# CANOPi_Baseboard_LTE.net
KiCad netlist of a schematic drawn in Altium Designer
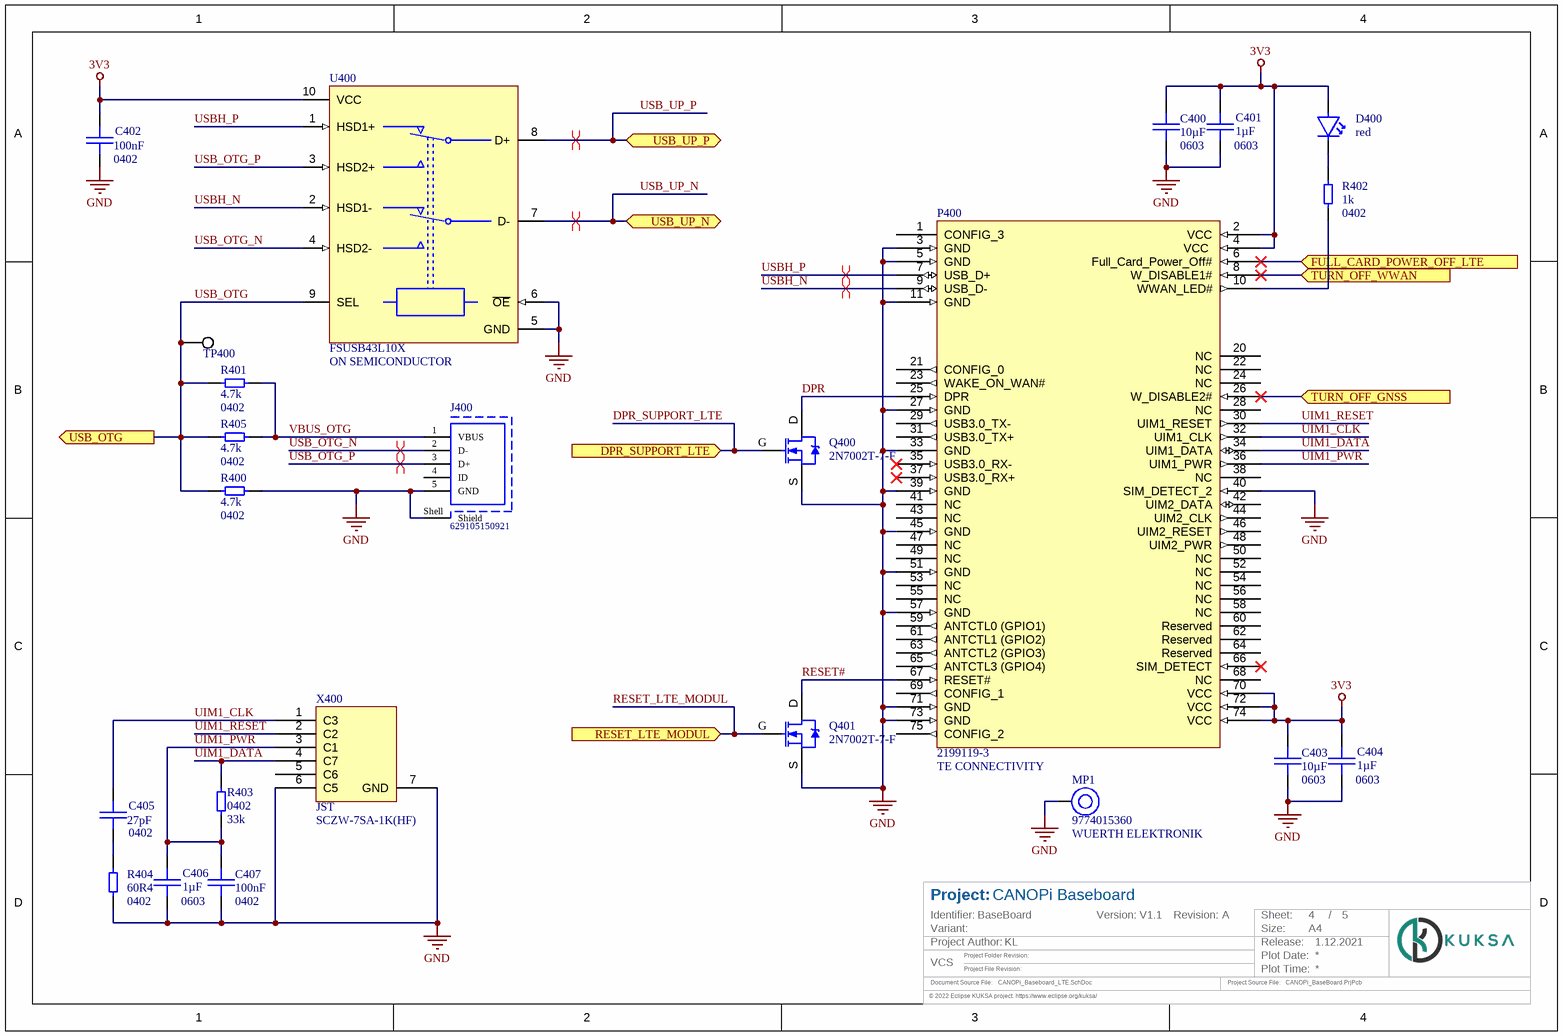
[diagram p0: CANOPi_Baseboard_LTE.SchDoc]

(export (version "E")
  (design (tool "Eeschema 10.0.6"))
  (components
    (comp (ref "C400")
      (value "CAP 0603 10µF -20% +20% 6.3V X5R")
      (footprint "CAP 0603 [1608 Metric] X080 N")
      (description "SMT 10µF ±20% 6,3 V Keramikkondensatoren X5R")
      (fields
        (field (name "MANUFACTURER PART NUMBER") "GRM188R60J106ME84")
        (field (name "CAPACITANCE") "10µF")
        (field (name "MANUFACTURER") "MURATA")
        (field (name "CASE") "0603")
      )
      (libsource (lib "ShareLib") (part "Capacitor non-polarized - Standard Schematic"))
    )
    (comp (ref "C401")
      (value "CAP 0603 1u -10% +10% 10V X7R")
      (footprint "CAP 0603 [1608 Metric] X080 N")
      (description "SMD/SMT 0603 10V -10% +10% X7R - Multilayer Ceramic Capacitors MLCC")
      (fields
        (field (name "CAPACITANCE") "1µF")
        (field (name "MANUFACTURER PART NUMBER") "GRM188R71A105KA61#")
        (field (name "MANUFACTURER") "MURATA")
        (field (name "CASE") "0603")
      )
      (libsource (lib "ShareLib") (part "Capacitor non-polarized - Standard Schematic"))
    )
    (comp (ref "C402")
      (value "CAP 0402 100n -10% +10% 6.3V X7R")
      (footprint "CAP 0402 [1005 Metric] X050 N")
      (description "SMD/SMT 0402 6.3V -10% +10% X7R - Multilayer Ceramic Capacitors MLCC")
      (fields
        (field (name "MANUFACTURER") "MURATA")
        (field (name "CAPACITANCE") "100nF")
        (field (name "MANUFACTURER PART NUMBER") "GRM155R70J104KA01#")
        (field (name "CASE") "0402")
      )
      (libsource (lib "ShareLib") (part "Capacitor non-polarized - Standard Schematic"))
    )
    (comp (ref "C403")
      (value "CAP 0603 10µF -20% +20% 6.3V X5R")
      (footprint "CAP 0603 [1608 Metric] X080 N")
      (description "SMT 10µF ±20% 6,3 V Keramikkondensatoren X5R")
      (fields
        (field (name "MANUFACTURER PART NUMBER") "GRM188R60J106ME84")
        (field (name "CAPACITANCE") "10µF")
        (field (name "MANUFACTURER") "MURATA")
        (field (name "CASE") "0603")
      )
      (libsource (lib "ShareLib") (part "Capacitor non-polarized - Standard Schematic"))
    )
    (comp (ref "C404")
      (value "CAP 0603 1u -10% +10% 10V X7R")
      (footprint "CAP 0603 [1608 Metric] X080 N")
      (description "SMD/SMT 0603 10V -10% +10% X7R - Multilayer Ceramic Capacitors MLCC")
      (fields
        (field (name "CAPACITANCE") "1µF")
        (field (name "MANUFACTURER PART NUMBER") "GRM188R71A105KA61#")
        (field (name "MANUFACTURER") "MURATA")
        (field (name "CASE") "0603")
      )
      (libsource (lib "ShareLib") (part "Capacitor non-polarized - Standard Schematic"))
    )
    (comp (ref "C405")
      (value "CAP 0402 27p -2% +2% 25V C0G")
      (footprint "CAP 0402 [1005 Metric] X050 N")
      (description "SMD/SMT 0402 25V -2% +2% C0G - Multilayer Ceramic Capacitors MLCC")
      (fields
        (field (name "MANUFACTURER") "MURATA")
        (field (name "CASE") "0402")
        (field (name "MANUFACTURER PART NUMBER") "GRM1555C1E270GA01#")
        (field (name "CAPACITANCE") "27pF")
      )
      (libsource (lib "ShareLib") (part "Capacitor non-polarized - Standard Schematic"))
    )
    (comp (ref "C406")
      (value "CAP 0603 1u -10% +10% 10V X7R")
      (footprint "CAP 0603 [1608 Metric] X080 N")
      (description "SMD/SMT 0603 10V -10% +10% X7R - Multilayer Ceramic Capacitors MLCC")
      (fields
        (field (name "CAPACITANCE") "1µF")
        (field (name "MANUFACTURER PART NUMBER") "GRM188R71A105KA61#")
        (field (name "MANUFACTURER") "MURATA")
        (field (name "CASE") "0603")
      )
      (libsource (lib "ShareLib") (part "Capacitor non-polarized - Standard Schematic"))
    )
    (comp (ref "C407")
      (value "CAP 0402 100n -10% +10% 6.3V X7R")
      (footprint "CAP 0402 [1005 Metric] X050 N")
      (description "SMD/SMT 0402 6.3V -10% +10% X7R - Multilayer Ceramic Capacitors MLCC")
      (fields
        (field (name "MANUFACTURER") "MURATA")
        (field (name "CAPACITANCE") "100nF")
        (field (name "MANUFACTURER PART NUMBER") "GRM155R70J104KA01#")
        (field (name "CASE") "0402")
      )
      (libsource (lib "ShareLib") (part "Capacitor non-polarized - Standard Schematic"))
    )
    (comp (ref "D400")
      (value "WUERTH ELEKTRONIK - 155124RS73200")
      (footprint "WUERTH ELEKTRONIK - WL-SMSW")
      (description "LED, RED, Right Angle SMD 3.2*1.0mm WL-SMSW SMT Mono-color Side view Waterclear")
      (fields
        (field (name "COLOUR LED1") "red")
        (field (name "MANUFACTURER") "WUERTH ELEKTRONIK")
        (field (name "MANUFACTURER PART NUMBER") "155124RS73200")
      )
      (libsource (lib "ShareLib") (part "LED - Standard Schematic"))
    )
    (comp (ref "J400")
      (value "629105150921")
      (footprint "629105150921")
      (description "Micro USB 2.0 Type AB Receptacle WR-COM, Horizontal, SMT")
      (fields (field (name "MANUFACTURER") "Wurth Elektronik") (field (name "PUBLISHER") "WurthElektronik"))
      (libsource (lib "Altium Content Vault") (part "WE-USB-5-1SHLD"))
    )
    (comp (ref "MP1")
      (value "WUERTH ELEKTRONIK - 9774015360")
      (footprint "WUERTH ELEKTRONIK - 9774015360")
      (description "WA-SMSI SMT Steel Spacer with internal Thread, OD 6mm, M3 x 1.5mm")
      (fields
        (field (name "MANUFACTURER PART NUMBER") "9774015360")
        (field (name "MANUFACTURER") "WUERTH ELEKTRONIK")
      )
      (libsource (lib "ShareLib") (part "WUERTH ELEKTRONIK - 9774015360"))
    )
    (comp (ref "P400")
      (value "TE CONNECTIVITY - 2199119-3")
      (footprint "M.2 (NGFF) Connectors")
      (fields
        (field (name "MANUFACTURER PART NUMBER") "2199119-3")
        (field (name "MANUFACTURER") "TE CONNECTIVITY")
      )
      (libsource (lib "ShareLib") (part "M.2 (NGFF) Connectors"))
    )
    (comp (ref "Q400")
      (value "DIODES INCORPORATED - 2N7002T")
      (footprint "DIODES INCORPORATED - SOT523")
      (description "N-CHANNEL ENHANCEMENT MODE FIELD EFFECT TRANSISTOR")
      (fields
        (field (name "MANUFACTURER") "DIODES INCORPORATED")
        (field (name "MANUFACTURER PART NUMBER") "2N7002T-7-F")
      )
      (libsource (lib "ShareLib") (part "N-Channel, 3-Pin MOSFET, Designator DSG"))
    )
    (comp (ref "Q401")
      (value "DIODES INCORPORATED - 2N7002T")
      (footprint "DIODES INCORPORATED - SOT523")
      (description "N-CHANNEL ENHANCEMENT MODE FIELD EFFECT TRANSISTOR")
      (fields
        (field (name "MANUFACTURER") "DIODES INCORPORATED")
        (field (name "MANUFACTURER PART NUMBER") "2N7002T-7-F")
      )
      (libsource (lib "ShareLib") (part "N-Channel, 3-Pin MOSFET, Designator DSG"))
    )
    (comp (ref "R400")
      (value "RES 0402 4K7 1% 0W0625")
      (footprint "RES 0402 [1005 Metric]_N")
      (description "RC0402 series chip resistor with lead-free terminations made by thick film process")
      (fields
        (field (name "RESISTANCE") "4.7k")
        (field (name "MANUFACTURER PART NUMBER") "RC0402FR-074K7L")
        (field (name "MANUFACTURER") "YAGEO")
        (field (name "CASE") "0402")
      )
      (libsource (lib "ShareLib") (part "Standard Schematic - Resistor Universal"))
    )
    (comp (ref "R401")
      (value "RES 0402 4K7 1% 0W0625")
      (footprint "RES 0402 [1005 Metric]_N")
      (description "RC0402 series chip resistor with lead-free terminations made by thick film process")
      (fields
        (field (name "RESISTANCE") "4.7k")
        (field (name "MANUFACTURER PART NUMBER") "RC0402FR-074K7L")
        (field (name "MANUFACTURER") "YAGEO")
        (field (name "CASE") "0402")
      )
      (libsource (lib "ShareLib") (part "Standard Schematic - Resistor Universal"))
    )
    (comp (ref "R402")
      (value "RES 0402 1K 1% 0W0625")
      (footprint "RES 0402 [1005 Metric]_N")
      (description "RC0402 series chip resistor with lead-free terminations made by thick film process")
      (fields
        (field (name "CASE") "0402")
        (field (name "MANUFACTURER PART NUMBER") "RC0402FR-071KL")
        (field (name "MANUFACTURER") "YAGEO")
        (field (name "RESISTANCE") "1k")
      )
      (libsource (lib "ShareLib") (part "Standard Schematic - Resistor Universal"))
    )
    (comp (ref "R403")
      (value "RES 0402 33K 1% 0W0625")
      (footprint "RES 0402 [1005 Metric]_N")
      (description "RC0402 series chip resistor with lead-free terminations made by thick film process")
      (fields
        (field (name "MANUFACTURER") "YAGEO")
        (field (name "CASE") "0402")
        (field (name "MANUFACTURER PART NUMBER") "RC0402FR-0733KL")
        (field (name "RESISTANCE") "33k")
      )
      (libsource (lib "ShareLib") (part "Standard Schematic - Resistor Universal"))
    )
    (comp (ref "R404")
      (value "RES 0402 60R4 1% 0W0625")
      (footprint "RES 0402 [1005 Metric]_N")
      (description "RC0402 series chip resistor with lead-free terminations made by thick film process")
      (fields
        (field (name "RESISTANCE") "60R4")
        (field (name "MANUFACTURER PART NUMBER") "RC0402FR-0760R4L")
        (field (name "MANUFACTURER") "YAGEO")
        (field (name "CASE") "0402")
      )
      (libsource (lib "ShareLib") (part "Standard Schematic - Resistor Universal"))
    )
    (comp (ref "R405")
      (value "RES 0402 4K7 1% 0W0625")
      (footprint "RES 0402 [1005 Metric]_N")
      (description "RC0402 series chip resistor with lead-free terminations made by thick film process")
      (fields
        (field (name "RESISTANCE") "4.7k")
        (field (name "MANUFACTURER PART NUMBER") "RC0402FR-074K7L")
        (field (name "MANUFACTURER") "YAGEO")
        (field (name "CASE") "0402")
      )
      (libsource (lib "ShareLib") (part "Standard Schematic - Resistor Universal"))
    )
    (comp (ref "TP400")
      (value "Testpad, 0.8mm x 0.8mm, round")
      (footprint "Testpad, 0.8mm x 0.8mm, round")
      (libsource (lib "ShareLib") (part "Testpoint (No BOM)"))
    )
    (comp (ref "U400")
      (value "ON SEMICONDUCTOR - FSUSB43L10X")
      (footprint "ON SEMICONDUCTOR - FSUSB43L10X")
      (description "Low-Power, Two-Port, High-Speed, USB2.0 (480Mbps) Switch")
      (fields
        (field (name "MANUFACTURER PART NUMBER") "FSUSB43L10X")
        (field (name "MANUFACTURER") "ON SEMICONDUCTOR")
      )
      (libsource (lib "ShareLib") (part "ON SEMICONDUCTOR - FSUSB43L10X"))
    )
    (comp (ref "X400")
      (value "JST - SCZW-7SA-1K(HF)")
      (footprint "JST SCZW-7SA-1K(HF)")
      (description "SIM-Kartenleser aufklappbar und sperrfähig")
      (fields (field (name "MANUFACTURER") "JST") (field (name "MANUFACTURER PART NUMBER") "SCZW-7SA-1K(HF)"))
      (libsource (lib "ShareLib") (part "JST SCZW-7SA-1K(HF)"))
    )
  )
  (nets
    (net (code "1") (name "/DPR") (class "Default")
      (node (ref "P400") (pin "25") (pinfunction "DPR_25") (pintype "input"))
      (node (ref "Q400") (pin "D") (pinfunction "D_D") (pintype "passive"))
    )
    (net (code "2") (name "/DPR_SUPPORT_LTE") (class "Default")
      (node (ref "Q400") (pin "G") (pinfunction "G_G") (pintype "passive"))
    )
    (net (code "3") (name "/FULL_CARD_POWER_OFF_LTE") (class "Default")
      (node (ref "P400") (pin "6") (pinfunction "Full_Card_Power_Off#_6") (pintype "input+no_connect"))
    )
    (net (code "4") (name "/RESET#") (class "Default")
      (node (ref "P400") (pin "67") (pinfunction "RESET#_67") (pintype "input"))
      (node (ref "Q401") (pin "D") (pinfunction "D_D") (pintype "passive"))
    )
    (net (code "5") (name "/RESET_LTE_MODUL") (class "Default")
      (node (ref "Q401") (pin "G") (pinfunction "G_G") (pintype "passive"))
    )
    (net (code "6") (name "/TURN_OFF_GNSS") (class "Default")
      (node (ref "P400") (pin "26") (pinfunction "W_DISABLE2#_26") (pintype "input+no_connect"))
    )
    (net (code "7") (name "/TURN_OFF_WWAN") (class "Default")
      (node (ref "P400") (pin "8") (pinfunction "W_DISABLE1#_8") (pintype "input+no_connect"))
    )
    (net (code "8") (name "/UIM1_CLK") (class "Default")
      (node (ref "C405") (pin "2") (pinfunction "2_2") (pintype "passive"))
      (node (ref "P400") (pin "32") (pinfunction "UIM1_CLK_32") (pintype "output"))
      (node (ref "X400") (pin "1") (pinfunction "C3_1") (pintype "passive"))
    )
    (net (code "9") (name "/UIM1_DATA") (class "Default")
      (node (ref "P400") (pin "34") (pinfunction "UIM1_DATA_34") (pintype "bidirectional"))
      (node (ref "R403") (pin "1") (pinfunction "1_1") (pintype "passive"))
      (node (ref "X400") (pin "4") (pinfunction "C7_4") (pintype "passive"))
    )
    (net (code "10") (name "/UIM1_PWR") (class "Default")
      (node (ref "C406") (pin "1") (pinfunction "1_1") (pintype "passive"))
      (node (ref "C407") (pin "1") (pinfunction "1_1") (pintype "passive"))
      (node (ref "P400") (pin "36") (pinfunction "UIM1_PWR_36") (pintype "output"))
      (node (ref "R403") (pin "2") (pinfunction "2_2") (pintype "passive"))
      (node (ref "X400") (pin "3") (pinfunction "C1_3") (pintype "passive"))
    )
    (net (code "11") (name "/UIM1_RESET") (class "Default")
      (node (ref "P400") (pin "30") (pinfunction "UIM1_RESET_30") (pintype "output"))
      (node (ref "X400") (pin "2") (pinfunction "C2_2") (pintype "passive"))
    )
    (net (code "12") (name "/USBH_N") (class "Default")
      (node (ref "P400") (pin "9") (pinfunction "USB_D-_9") (pintype "bidirectional"))
      (node (ref "U400") (pin "2") (pinfunction "HSD1-_2") (pintype "input"))
    )
    (net (code "13") (name "/USBH_P") (class "Default")
      (node (ref "P400") (pin "7") (pinfunction "USB_D+_7") (pintype "bidirectional"))
      (node (ref "U400") (pin "1") (pinfunction "HSD1+_1") (pintype "input"))
    )
    (net (code "14") (name "/USB_OTG") (class "Default")
      (node (ref "R400") (pin "2") (pinfunction "2_2") (pintype "passive"))
      (node (ref "R401") (pin "2") (pinfunction "2_2") (pintype "passive"))
      (node (ref "R405") (pin "2") (pinfunction "2_2") (pintype "passive"))
      (node (ref "TP400") (pin "1") (pinfunction "1_1") (pintype "passive"))
      (node (ref "U400") (pin "9") (pinfunction "SEL_9") (pintype "passive"))
    )
    (net (code "15") (name "/USB_OTG_N") (class "Default")
      (node (ref "J400") (pin "2") (pinfunction "D-_2") (pintype "passive"))
      (node (ref "U400") (pin "4") (pinfunction "HSD2-_4") (pintype "input"))
    )
    (net (code "16") (name "/USB_OTG_P") (class "Default")
      (node (ref "J400") (pin "3") (pinfunction "D+_3") (pintype "passive"))
      (node (ref "U400") (pin "3") (pinfunction "HSD2+_3") (pintype "input"))
    )
    (net (code "17") (name "/USB_UP_N") (class "Default")
      (node (ref "U400") (pin "7") (pinfunction "D-_7") (pintype "passive"))
    )
    (net (code "18") (name "/USB_UP_P") (class "Default")
      (node (ref "U400") (pin "8") (pinfunction "D+_8") (pintype "passive"))
    )
    (net (code "19") (name "/VBUS_OTG") (class "Default")
      (node (ref "J400") (pin "1") (pinfunction "VBUS_1") (pintype "passive"))
      (node (ref "R401") (pin "1") (pinfunction "1_1") (pintype "passive"))
      (node (ref "R405") (pin "1") (pinfunction "1_1") (pintype "passive"))
    )
    (net (code "20") (name "3V3") (class "Default")
      (node (ref "C400") (pin "1") (pinfunction "1_1") (pintype "passive"))
      (node (ref "C401") (pin "1") (pinfunction "1_1") (pintype "passive"))
      (node (ref "C402") (pin "2") (pinfunction "2_2") (pintype "passive"))
      (node (ref "C403") (pin "1") (pinfunction "1_1") (pintype "passive"))
      (node (ref "C404") (pin "1") (pinfunction "1_1") (pintype "passive"))
      (node (ref "D400") (pin "A") (pinfunction "A_A") (pintype "passive"))
      (node (ref "P400") (pin "2") (pinfunction "VCC_2") (pintype "input"))
      (node (ref "P400") (pin "4") (pinfunction "VCC_4") (pintype "input"))
      (node (ref "P400") (pin "70") (pinfunction "VCC_70") (pintype "input"))
      (node (ref "P400") (pin "72") (pinfunction "VCC_72") (pintype "input"))
      (node (ref "P400") (pin "74") (pinfunction "VCC_74") (pintype "input"))
      (node (ref "U400") (pin "10") (pinfunction "VCC_10") (pintype "power_in"))
    )
    (net (code "21") (name "GND") (class "Default")
      (node (ref "C400") (pin "2") (pinfunction "2_2") (pintype "passive"))
      (node (ref "C401") (pin "2") (pinfunction "2_2") (pintype "passive"))
      (node (ref "C402") (pin "1") (pinfunction "1_1") (pintype "passive"))
      (node (ref "C403") (pin "2") (pinfunction "2_2") (pintype "passive"))
      (node (ref "C404") (pin "2") (pinfunction "2_2") (pintype "passive"))
      (node (ref "C406") (pin "2") (pinfunction "2_2") (pintype "passive"))
      (node (ref "C407") (pin "2") (pinfunction "2_2") (pintype "passive"))
      (node (ref "J400") (pin "5") (pinfunction "GND_5") (pintype "passive"))
      (node (ref "J400") (pin "Shell") (pinfunction "Shield_Shell") (pintype "passive"))
      (node (ref "MP1") (pin "1") (pinfunction "1_1") (pintype "passive"))
      (node (ref "P400") (pin "11") (pinfunction "GND_11") (pintype "input"))
      (node (ref "P400") (pin "27") (pinfunction "GND_27") (pintype "input"))
      (node (ref "P400") (pin "3") (pinfunction "GND_3") (pintype "input"))
      (node (ref "P400") (pin "33") (pinfunction "GND_33") (pintype "passive"))
      (node (ref "P400") (pin "39") (pinfunction "GND_39") (pintype "input"))
      (node (ref "P400") (pin "40") (pinfunction "SIM_DETECT_2_40") (pintype "input"))
      (node (ref "P400") (pin "45") (pinfunction "GND_45") (pintype "input"))
      (node (ref "P400") (pin "5") (pinfunction "GND_5") (pintype "input"))
      (node (ref "P400") (pin "51") (pinfunction "GND_51") (pintype "input"))
      (node (ref "P400") (pin "57") (pinfunction "GND_57") (pintype "input"))
      (node (ref "P400") (pin "71") (pinfunction "GND_71") (pintype "input"))
      (node (ref "P400") (pin "73") (pinfunction "GND_73") (pintype "input"))
      (node (ref "Q400") (pin "S") (pinfunction "S_S") (pintype "passive"))
      (node (ref "Q401") (pin "S") (pinfunction "S_S") (pintype "passive"))
      (node (ref "R400") (pin "1") (pinfunction "1_1") (pintype "passive"))
      (node (ref "R404") (pin "1") (pinfunction "1_1") (pintype "passive"))
      (node (ref "U400") (pin "5") (pinfunction "GND_5") (pintype "power_in"))
      (node (ref "U400") (pin "6") (pinfunction "~{OE}_6") (pintype "input"))
      (node (ref "X400") (pin "6") (pinfunction "C5_6") (pintype "passive"))
      (node (ref "X400") (pin "7") (pinfunction "GND_7") (pintype "passive"))
    )
    (net (code "22") (name "Net-(C405-Pad1)") (class "Default")
      (node (ref "C405") (pin "1") (pinfunction "1_1") (pintype "passive"))
      (node (ref "R404") (pin "2") (pinfunction "2_2") (pintype "passive"))
    )
    (net (code "23") (name "Net-(D400-PadC)") (class "Default")
      (node (ref "D400") (pin "C") (pinfunction "C_C") (pintype "passive"))
      (node (ref "R402") (pin "2") (pinfunction "2_2") (pintype "passive"))
    )
    (net (code "24") (name "Net-(P400-WWAN_LED#)") (class "Default")
      (node (ref "P400") (pin "10") (pinfunction "WWAN_LED#_10") (pintype "output"))
      (node (ref "R402") (pin "1") (pinfunction "1_1") (pintype "passive"))
    )
    (net (code "25") (name "unconnected-(J400-ID-Pad4)") (class "Default")
      (node (ref "J400") (pin "4") (pinfunction "ID_4") (pintype "passive"))
    )
    (net (code "26") (name "unconnected-(P400-ANTCTL0_(GPIO1)-Pad59)") (class "Default")
      (node (ref "P400") (pin "59") (pinfunction "ANTCTL0_(GPIO1)_59") (pintype "output"))
    )
    (net (code "27") (name "unconnected-(P400-ANTCTL1_(GPIO2)-Pad61)") (class "Default")
      (node (ref "P400") (pin "61") (pinfunction "ANTCTL1_(GPIO2)_61") (pintype "output"))
    )
    (net (code "28") (name "unconnected-(P400-ANTCTL2_(GPIO3)-Pad63)") (class "Default")
      (node (ref "P400") (pin "63") (pinfunction "ANTCTL2_(GPIO3)_63") (pintype "output"))
    )
    (net (code "29") (name "unconnected-(P400-ANTCTL3_(GPIO4)-Pad65)") (class "Default")
      (node (ref "P400") (pin "65") (pinfunction "ANTCTL3_(GPIO4)_65") (pintype "output"))
    )
    (net (code "30") (name "unconnected-(P400-CONFIG_0-Pad21)") (class "Default")
      (node (ref "P400") (pin "21") (pinfunction "CONFIG_0_21") (pintype "output"))
    )
    (net (code "31") (name "unconnected-(P400-CONFIG_1-Pad69)") (class "Default")
      (node (ref "P400") (pin "69") (pinfunction "CONFIG_1_69") (pintype "output"))
    )
    (net (code "32") (name "unconnected-(P400-CONFIG_2-Pad75)") (class "Default")
      (node (ref "P400") (pin "75") (pinfunction "CONFIG_2_75") (pintype "output"))
    )
    (net (code "33") (name "unconnected-(P400-CONFIG_3-Pad1)") (class "Default")
      (node (ref "P400") (pin "1") (pinfunction "CONFIG_3_1") (pintype "passive"))
    )
    (net (code "34") (name "unconnected-(P400-NC-Pad20)") (class "Default")
      (node (ref "P400") (pin "20") (pinfunction "NC_20") (pintype "passive"))
    )
    (net (code "35") (name "unconnected-(P400-NC-Pad22)") (class "Default")
      (node (ref "P400") (pin "22") (pinfunction "NC_22") (pintype "passive"))
    )
    (net (code "36") (name "unconnected-(P400-NC-Pad24)") (class "Default")
      (node (ref "P400") (pin "24") (pinfunction "NC_24") (pintype "passive"))
    )
    (net (code "37") (name "unconnected-(P400-NC-Pad28)") (class "Default")
      (node (ref "P400") (pin "28") (pinfunction "NC_28") (pintype "passive"))
    )
    (net (code "38") (name "unconnected-(P400-NC-Pad38)") (class "Default")
      (node (ref "P400") (pin "38") (pinfunction "NC_38") (pintype "passive"))
    )
    (net (code "39") (name "unconnected-(P400-NC-Pad41)") (class "Default")
      (node (ref "P400") (pin "41") (pinfunction "NC_41") (pintype "passive"))
    )
    (net (code "40") (name "unconnected-(P400-NC-Pad43)") (class "Default")
      (node (ref "P400") (pin "43") (pinfunction "NC_43") (pintype "passive"))
    )
    (net (code "41") (name "unconnected-(P400-NC-Pad47)") (class "Default")
      (node (ref "P400") (pin "47") (pinfunction "NC_47") (pintype "passive"))
    )
    (net (code "42") (name "unconnected-(P400-NC-Pad49)") (class "Default")
      (node (ref "P400") (pin "49") (pinfunction "NC_49") (pintype "passive"))
    )
    (net (code "43") (name "unconnected-(P400-NC-Pad50)") (class "Default")
      (node (ref "P400") (pin "50") (pinfunction "NC_50") (pintype "passive"))
    )
    (net (code "44") (name "unconnected-(P400-NC-Pad52)") (class "Default")
      (node (ref "P400") (pin "52") (pinfunction "NC_52") (pintype "passive"))
    )
    (net (code "45") (name "unconnected-(P400-NC-Pad53)") (class "Default")
      (node (ref "P400") (pin "53") (pinfunction "NC_53") (pintype "passive"))
    )
    (net (code "46") (name "unconnected-(P400-NC-Pad54)") (class "Default")
      (node (ref "P400") (pin "54") (pinfunction "NC_54") (pintype "passive"))
    )
    (net (code "47") (name "unconnected-(P400-NC-Pad55)") (class "Default")
      (node (ref "P400") (pin "55") (pinfunction "NC_55") (pintype "passive"))
    )
    (net (code "48") (name "unconnected-(P400-NC-Pad56)") (class "Default")
      (node (ref "P400") (pin "56") (pinfunction "NC_56") (pintype "passive"))
    )
    (net (code "49") (name "unconnected-(P400-NC-Pad58)") (class "Default")
      (node (ref "P400") (pin "58") (pinfunction "NC_58") (pintype "passive"))
    )
    (net (code "50") (name "unconnected-(P400-NC-Pad68)") (class "Default")
      (node (ref "P400") (pin "68") (pinfunction "NC_68") (pintype "passive"))
    )
    (net (code "51") (name "unconnected-(P400-Reserved-Pad60)") (class "Default")
      (node (ref "P400") (pin "60") (pinfunction "Reserved_60") (pintype "passive"))
    )
    (net (code "52") (name "unconnected-(P400-Reserved-Pad62)") (class "Default")
      (node (ref "P400") (pin "62") (pinfunction "Reserved_62") (pintype "passive"))
    )
    (net (code "53") (name "unconnected-(P400-Reserved-Pad64)") (class "Default")
      (node (ref "P400") (pin "64") (pinfunction "Reserved_64") (pintype "passive"))
    )
    (net (code "54") (name "unconnected-(P400-SIM_DETECT-Pad66)") (class "Default")
      (node (ref "P400") (pin "66") (pinfunction "SIM_DETECT_66") (pintype "input+no_connect"))
    )
    (net (code "55") (name "unconnected-(P400-UIM2_CLK-Pad44)") (class "Default")
      (node (ref "P400") (pin "44") (pinfunction "UIM2_CLK_44") (pintype "output"))
    )
    (net (code "56") (name "unconnected-(P400-UIM2_DATA-Pad42)") (class "Default")
      (node (ref "P400") (pin "42") (pinfunction "UIM2_DATA_42") (pintype "bidirectional"))
    )
    (net (code "57") (name "unconnected-(P400-UIM2_PWR-Pad48)") (class "Default")
      (node (ref "P400") (pin "48") (pinfunction "UIM2_PWR_48") (pintype "output"))
    )
    (net (code "58") (name "unconnected-(P400-UIM2_RESET-Pad46)") (class "Default")
      (node (ref "P400") (pin "46") (pinfunction "UIM2_RESET_46") (pintype "output"))
    )
    (net (code "59") (name "unconnected-(P400-USB3.0_RX+-Pad37)") (class "Default")
      (node (ref "P400") (pin "37") (pinfunction "USB3.0_RX+_37") (pintype "input+no_connect"))
    )
    (net (code "60") (name "unconnected-(P400-USB3.0_RX--Pad35)") (class "Default")
      (node (ref "P400") (pin "35") (pinfunction "USB3.0_RX-_35") (pintype "input+no_connect"))
    )
    (net (code "61") (name "unconnected-(P400-USB3.0_TX+-Pad31)") (class "Default")
      (node (ref "P400") (pin "31") (pinfunction "USB3.0_TX+_31") (pintype "output"))
    )
    (net (code "62") (name "unconnected-(P400-USB3.0_TX--Pad29)") (class "Default")
      (node (ref "P400") (pin "29") (pinfunction "USB3.0_TX-_29") (pintype "output"))
    )
    (net (code "63") (name "unconnected-(P400-WAKE_ON_WAN#-Pad23)") (class "Default")
      (node (ref "P400") (pin "23") (pinfunction "WAKE_ON_WAN#_23") (pintype "output"))
    )
    (net (code "64") (name "unconnected-(X400-C6-Pad5)") (class "Default")
      (node (ref "X400") (pin "5") (pinfunction "C6_5") (pintype "passive"))
    )
  )
)
